# Sheet.net
KiCad netlist of a schematic drawn in Altium Designer
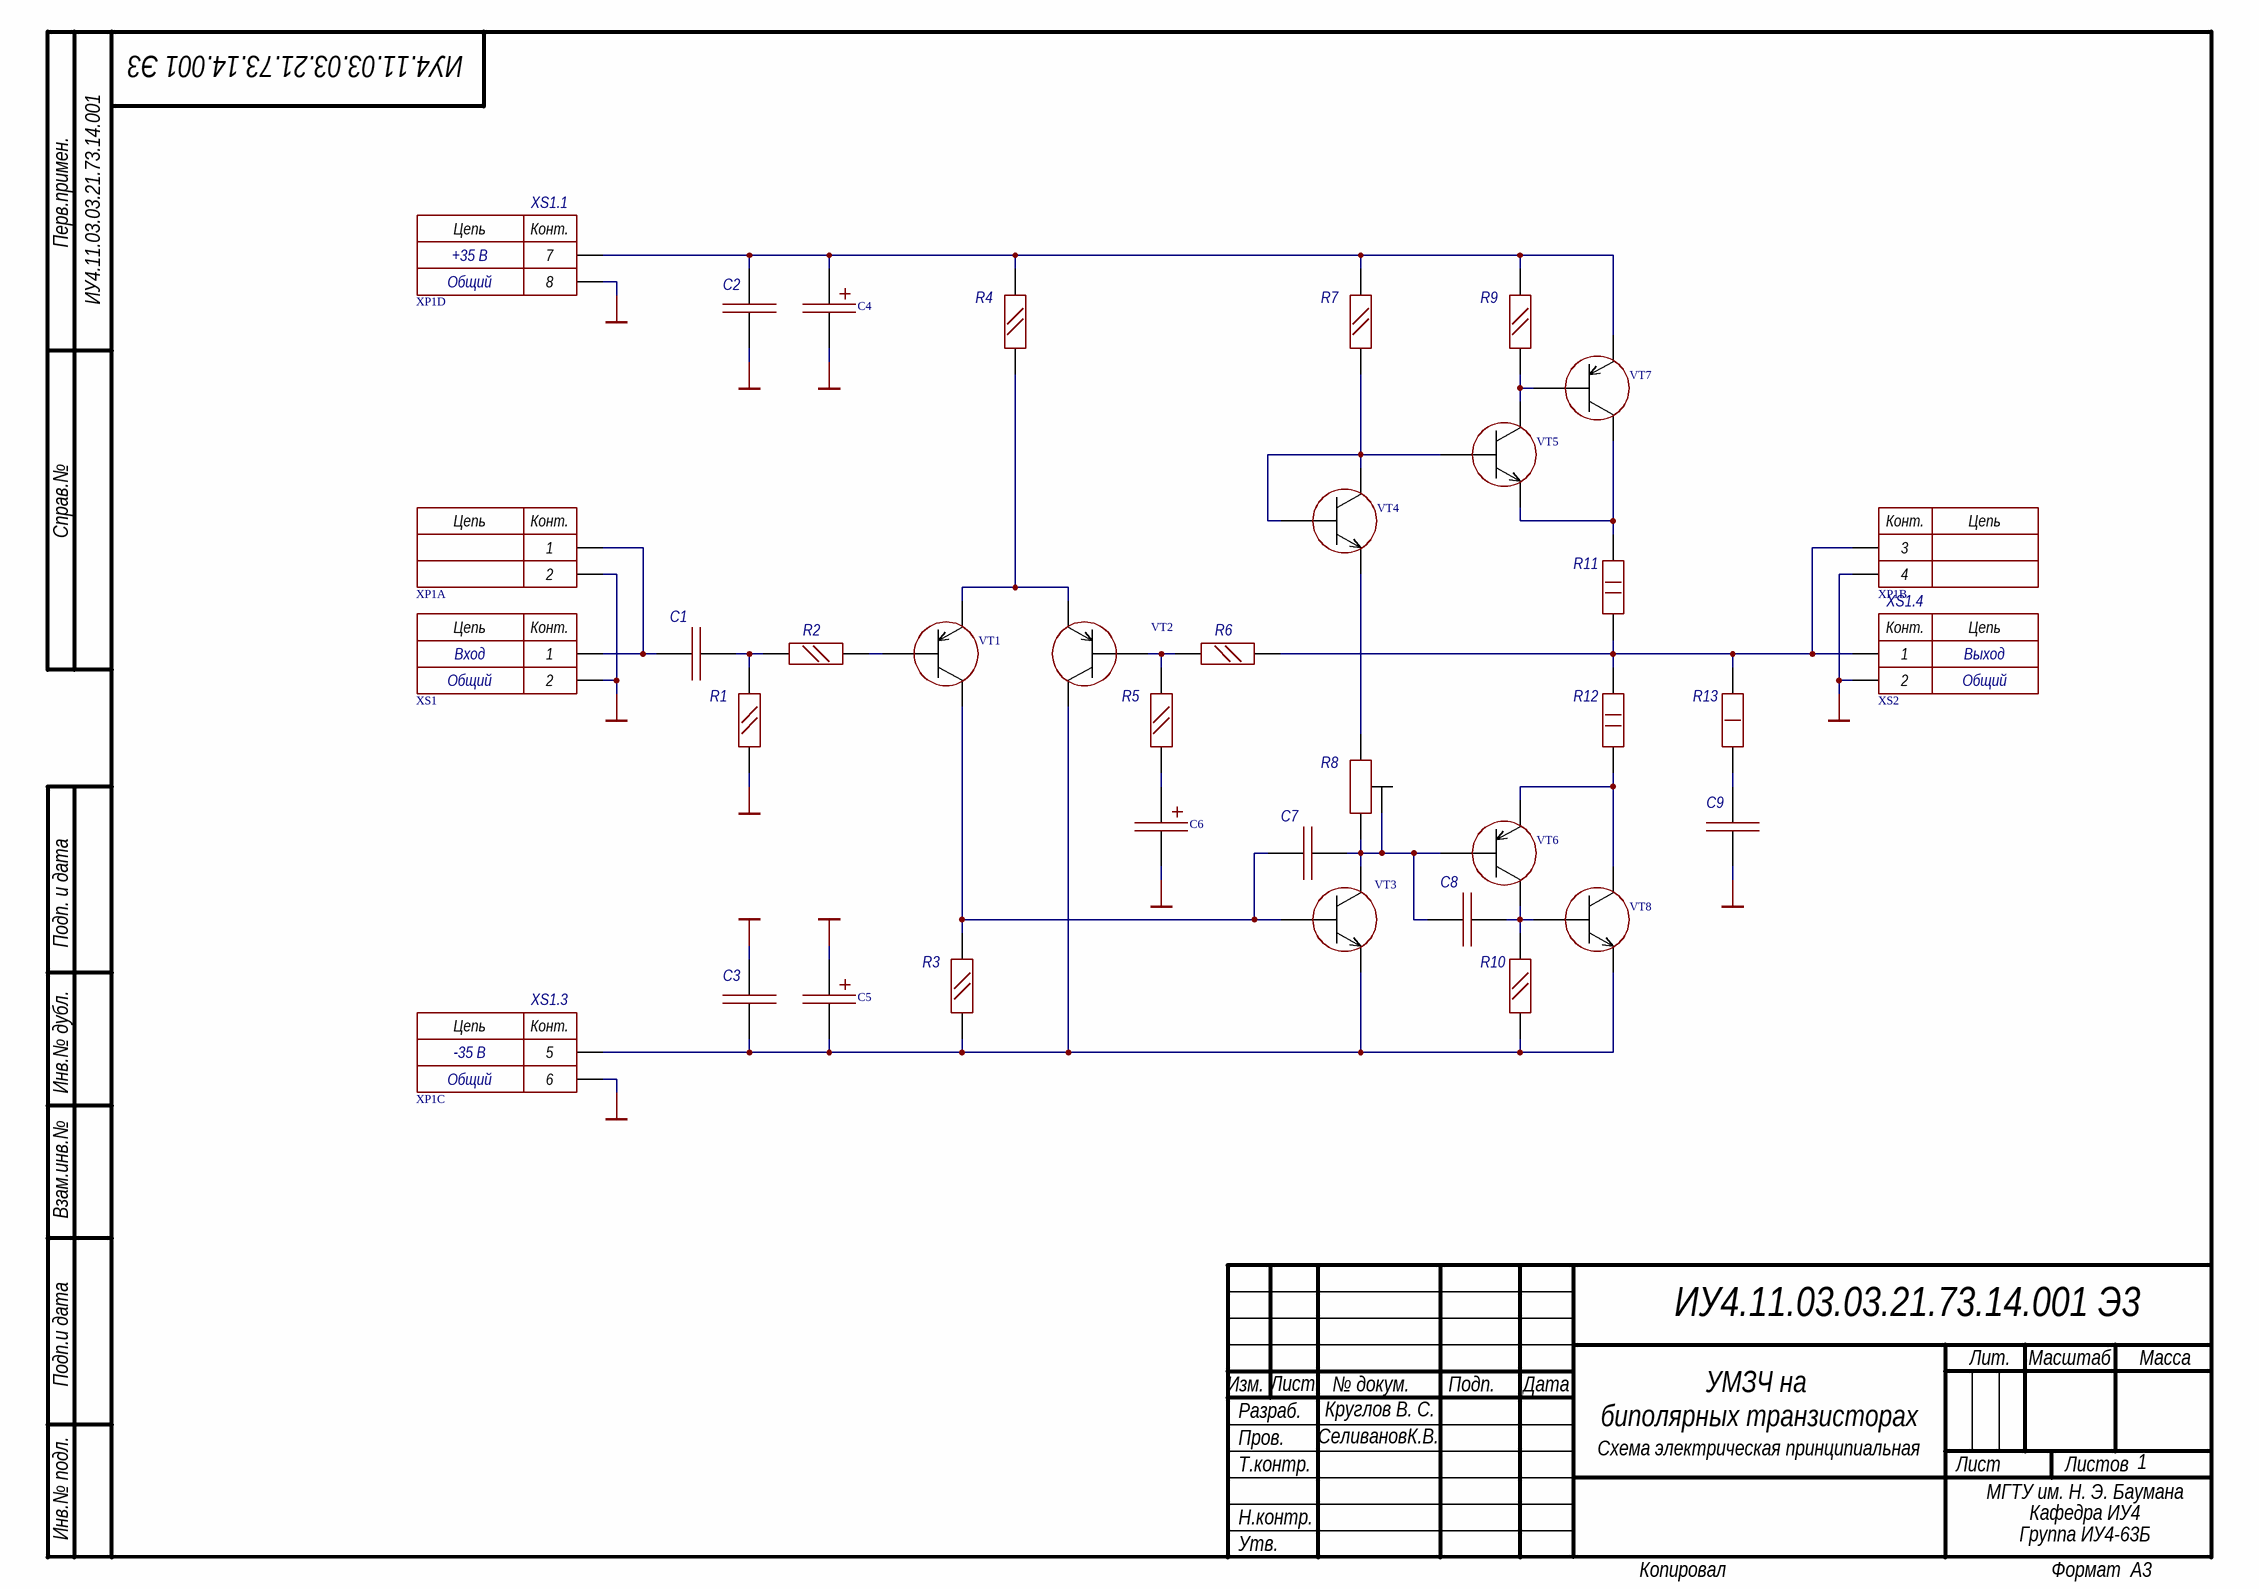
[diagram p0: Sheet.SchDoc]

(export (version "E")
  (design (tool "Eeschema 10.0.6"))
  (components
    (comp (ref "C1")
      (value "Capacitor")
      (footprint "C_PLY_10X5")
      (libsource (lib "Components - 07.07.24 - 20.56") (part "Capacitor"))
    )
    (comp (ref "C2")
      (value "Capacitor")
      (footprint "C_PLY_10X5")
      (libsource (lib "Components - 07.07.24 - 20.56") (part "Capacitor"))
    )
    (comp (ref "C3")
      (value "Capacitor")
      (footprint "C_PLY_10X5")
      (libsource (lib "Components - 07.07.24 - 20.56") (part "Capacitor"))
    )
    (comp (ref "C4")
      (value "Capactor polar")
      (footprint "C_EL_12X25")
      (libsource (lib "Components - 07.07.24 - 20.56") (part "Capactor polar"))
    )
    (comp (ref "C5")
      (value "Capactor polar")
      (footprint "C_EL_12X25")
      (libsource (lib "Components - 07.07.24 - 20.56") (part "Capactor polar"))
    )
    (comp (ref "C6")
      (value "Capactor polar")
      (footprint "C_EL_4X7")
      (libsource (lib "Components - 07.07.24 - 20.56") (part "Capactor polar"))
    )
    (comp (ref "C7")
      (value "Capacitor")
      (footprint "C_PLY_7X5")
      (libsource (lib "Components - 07.07.24 - 20.56") (part "Capacitor"))
    )
    (comp (ref "C8")
      (value "Capacitor")
      (footprint "C_PLY_7X5")
      (libsource (lib "Components - 07.07.24 - 20.56") (part "Capacitor"))
    )
    (comp (ref "C9")
      (value "Capacitor")
      (footprint "C_PLY_10X5")
      (libsource (lib "Components - 07.07.24 - 20.56") (part "Capacitor"))
    )
    (comp (ref "R1")
      (value "Res")
      (footprint "R0125W_AX025")
      (libsource (lib "Integrated_Library_PAAF") (part "Res"))
    )
    (comp (ref "R2") (value "Res") (footprint "R0125W_AX025") (libsource (lib "") (part "Res_1")))
    (comp (ref "R3")
      (value "Res")
      (footprint "R0125W_AX025")
      (libsource (lib "Integrated_Library_PAAF") (part "Res"))
    )
    (comp (ref "R4")
      (value "Res")
      (footprint "R0125W_AX025")
      (libsource (lib "Integrated_Library_PAAF") (part "Res"))
    )
    (comp (ref "R5")
      (value "Res")
      (footprint "R0125W_AX025")
      (libsource (lib "Integrated_Library_PAAF") (part "Res"))
    )
    (comp (ref "R6") (value "Res") (footprint "R0125W_AX025") (libsource (lib "") (part "Res_1")))
    (comp (ref "R7")
      (value "Res")
      (footprint "R0125W_AX025")
      (libsource (lib "Integrated_Library_PAAF") (part "Res"))
    )
    (comp (ref "R8")
      (value "POT")
      (footprint "POT_3296W")
      (libsource (lib "Integrated_Library_PAAF") (part "POT"))
    )
    (comp (ref "R9")
      (value "Res")
      (footprint "R0125W_AX025")
      (libsource (lib "Integrated_Library_PAAF") (part "Res"))
    )
    (comp (ref "R10")
      (value "Res")
      (footprint "R0125W_AX025")
      (libsource (lib "Integrated_Library_PAAF") (part "Res"))
    )
    (comp (ref "R11")
      (value "Res")
      (footprint "R2W_AX08")
      (libsource (lib "Integrated_Library_PAAF") (part "Res"))
    )
    (comp (ref "R12")
      (value "Res")
      (footprint "R2W_AX08")
      (libsource (lib "Integrated_Library_PAAF") (part "Res"))
    )
    (comp (ref "R13")
      (value "Res")
      (footprint "R1W_AX06")
      (libsource (lib "Integrated_Library_PAAF") (part "Res"))
    )
    (comp (ref "VT1")
      (value "Transistor_PNP")
      (footprint "TO92_3FB")
      (libsource (lib "Sch") (part "Transistor_PNP"))
    )
    (comp (ref "VT2")
      (value "Transistor_PNP")
      (footprint "TO92_3FB")
      (libsource (lib "Sch") (part "Transistor_PNP"))
    )
    (comp (ref "VT3")
      (value "BD139G")
      (footprint "TO220_3")
      (libsource (lib "Components - 07.07.24 - 21.07") (part "Transistor_NPN"))
    )
    (comp (ref "VT4")
      (value "BD139G")
      (footprint "TO126_3")
      (libsource (lib "Components - 07.07.24 - 21.07") (part "Transistor_NPN"))
    )
    (comp (ref "VT5")
      (value "BD139G")
      (footprint "TO126_3")
      (libsource (lib "Components - 07.07.24 - 21.07") (part "Transistor_NPN"))
    )
    (comp (ref "VT6")
      (value "Transistor_PNP")
      (footprint "TO126_3")
      (libsource (lib "Sch") (part "Transistor_PNP"))
    )
    (comp (ref "VT7")
      (value "Transistor_PNP")
      (footprint "TO247_3")
      (libsource (lib "Sch") (part "Transistor_PNP"))
    )
    (comp (ref "VT8")
      (value "BD139G")
      (footprint "TO247_3")
      (libsource (lib "Components - 07.07.24 - 21.07") (part "Transistor_NPN"))
    )
    (comp (ref "XP1")
      (value "CONN")
      (footprint "MOLEX_430450821")
      (libsource (lib "Components - 07.07.24 - 20.56") (part "CONN"))
    )
    (comp (ref "XS1")
      (value "Audio")
      (footprint "FP-NMJ4HFD2-MFG")
      (libsource (lib "Integrated_Library_PAAF") (part "Audio"))
    )
    (comp (ref "XS2")
      (value "Audio")
      (footprint "FP-NMJ4HFD2-MFG")
      (libsource (lib "Integrated_Library_PAAF") (part "Audio"))
    )
  )
  (nets
    (net (code "1") (name "GND") (class "Default")
      (node (ref "C2") (pin "2") (pinfunction "2_2") (pintype "passive"))
      (node (ref "C3") (pin "2") (pinfunction "2_2") (pintype "passive"))
      (node (ref "C4") (pin "1") (pinfunction "1_1") (pintype "passive"))
      (node (ref "C5") (pin "2") (pinfunction "2_2") (pintype "passive"))
      (node (ref "C6") (pin "1") (pinfunction "1_1") (pintype "passive"))
      (node (ref "C9") (pin "2") (pinfunction "2_2") (pintype "passive"))
      (node (ref "R1") (pin "1") (pinfunction "1_1") (pintype "passive"))
      (node (ref "XP1") (pin "2") (pintype "passive"))
      (node (ref "XP1") (pin "4") (pintype "passive"))
      (node (ref "XP1") (pin "6") (pintype "passive"))
      (node (ref "XP1") (pin "8") (pintype "passive"))
      (node (ref "XS1") (pin "2") (pintype "passive"))
      (node (ref "XS2") (pin "2") (pintype "passive"))
    )
    (net (code "2") (name "Net-(C1-Pad1)") (class "Default")
      (node (ref "C1") (pin "1") (pinfunction "1_1") (pintype "passive"))
      (node (ref "XP1") (pin "1") (pintype "passive"))
      (node (ref "XS1") (pin "1") (pintype "passive"))
    )
    (net (code "3") (name "Net-(C1-Pad2)") (class "Default")
      (node (ref "C1") (pin "2") (pinfunction "2_2") (pintype "passive"))
      (node (ref "R1") (pin "2") (pinfunction "2_2") (pintype "passive"))
      (node (ref "R2") (pin "2") (pinfunction "2_2") (pintype "passive"))
    )
    (net (code "4") (name "Net-(C6-Pad2)") (class "Default")
      (node (ref "C6") (pin "2") (pinfunction "2_2") (pintype "passive"))
      (node (ref "R5") (pin "1") (pinfunction "1_1") (pintype "passive"))
    )
    (net (code "5") (name "Net-(C9-Pad1)") (class "Default")
      (node (ref "C9") (pin "1") (pinfunction "1_1") (pintype "passive"))
      (node (ref "R13") (pin "1") (pinfunction "1_1") (pintype "passive"))
    )
    (net (code "6") (name "Net-(R11-Pad1)") (class "Default")
      (node (ref "R11") (pin "1") (pinfunction "1_1") (pintype "passive"))
      (node (ref "R12") (pin "2") (pinfunction "2_2") (pintype "passive"))
      (node (ref "R13") (pin "2") (pinfunction "2_2") (pintype "passive"))
      (node (ref "R6") (pin "1") (pinfunction "1_1") (pintype "passive"))
      (node (ref "XP1") (pin "3") (pintype "passive"))
      (node (ref "XS2") (pin "1") (pintype "passive"))
    )
    (net (code "7") (name "Net-(VT1-B)") (class "Default")
      (node (ref "R2") (pin "1") (pinfunction "1_1") (pintype "passive"))
      (node (ref "VT1") (pin "3") (pinfunction "B_3") (pintype "passive"))
    )
    (net (code "8") (name "Net-(VT1-C)") (class "Default")
      (node (ref "C7") (pin "1") (pinfunction "1_1") (pintype "passive"))
      (node (ref "R3") (pin "2") (pinfunction "2_2") (pintype "passive"))
      (node (ref "VT1") (pin "2") (pinfunction "C_2") (pintype "passive"))
      (node (ref "VT3") (pin "3") (pinfunction "B_3") (pintype "passive"))
    )
    (net (code "9") (name "Net-(VT1-E)") (class "Default")
      (node (ref "R4") (pin "1") (pinfunction "1_1") (pintype "passive"))
      (node (ref "VT1") (pin "1") (pinfunction "E_1") (pintype "passive"))
      (node (ref "VT2") (pin "1") (pinfunction "E_1") (pintype "passive"))
    )
    (net (code "10") (name "Net-(VT2-B)") (class "Default")
      (node (ref "R5") (pin "2") (pinfunction "2_2") (pintype "passive"))
      (node (ref "R6") (pin "2") (pinfunction "2_2") (pintype "passive"))
      (node (ref "VT2") (pin "3") (pinfunction "B_3") (pintype "passive"))
    )
    (net (code "11") (name "Net-(VT2-C)") (class "Default")
      (node (ref "C3") (pin "1") (pinfunction "1_1") (pintype "passive"))
      (node (ref "C5") (pin "1") (pinfunction "1_1") (pintype "passive"))
      (node (ref "R10") (pin "1") (pinfunction "1_1") (pintype "passive"))
      (node (ref "R3") (pin "1") (pinfunction "1_1") (pintype "passive"))
      (node (ref "VT2") (pin "2") (pinfunction "C_2") (pintype "passive"))
      (node (ref "VT3") (pin "1") (pinfunction "E_1") (pintype "passive"))
      (node (ref "VT8") (pin "1") (pinfunction "E_1") (pintype "passive"))
      (node (ref "XP1") (pin "5") (pintype "passive"))
    )
    (net (code "12") (name "Net-(VT3-C)") (class "Default")
      (node (ref "C7") (pin "2") (pinfunction "2_2") (pintype "passive"))
      (node (ref "C8") (pin "1") (pinfunction "1_1") (pintype "passive"))
      (node (ref "R8") (pin "2") (pinfunction "2_2") (pintype "passive"))
      (node (ref "R8") (pin "3") (pinfunction "3_3") (pintype "passive"))
      (node (ref "VT3") (pin "2") (pinfunction "C_2") (pintype "passive"))
      (node (ref "VT6") (pin "3") (pinfunction "B_3") (pintype "passive"))
    )
    (net (code "13") (name "Net-(VT4-B)") (class "Default")
      (node (ref "R7") (pin "1") (pinfunction "1_1") (pintype "passive"))
      (node (ref "VT4") (pin "2") (pinfunction "C_2") (pintype "passive"))
      (node (ref "VT4") (pin "3") (pinfunction "B_3") (pintype "passive"))
      (node (ref "VT5") (pin "3") (pinfunction "B_3") (pintype "passive"))
    )
    (net (code "14") (name "Net-(VT4-E)") (class "Default")
      (node (ref "R8") (pin "1") (pinfunction "1_1") (pintype "passive"))
      (node (ref "VT4") (pin "1") (pinfunction "E_1") (pintype "passive"))
    )
    (net (code "15") (name "Net-(VT5-C)") (class "Default")
      (node (ref "R9") (pin "1") (pinfunction "1_1") (pintype "passive"))
      (node (ref "VT5") (pin "2") (pinfunction "C_2") (pintype "passive"))
      (node (ref "VT7") (pin "3") (pinfunction "B_3") (pintype "passive"))
    )
    (net (code "16") (name "Net-(VT5-E)") (class "Default")
      (node (ref "R11") (pin "2") (pinfunction "2_2") (pintype "passive"))
      (node (ref "VT5") (pin "1") (pinfunction "E_1") (pintype "passive"))
      (node (ref "VT7") (pin "2") (pinfunction "C_2") (pintype "passive"))
    )
    (net (code "17") (name "Net-(VT6-C)") (class "Default")
      (node (ref "C8") (pin "2") (pinfunction "2_2") (pintype "passive"))
      (node (ref "R10") (pin "2") (pinfunction "2_2") (pintype "passive"))
      (node (ref "VT6") (pin "2") (pinfunction "C_2") (pintype "passive"))
      (node (ref "VT8") (pin "3") (pinfunction "B_3") (pintype "passive"))
    )
    (net (code "18") (name "Net-(VT6-E)") (class "Default")
      (node (ref "R12") (pin "1") (pinfunction "1_1") (pintype "passive"))
      (node (ref "VT6") (pin "1") (pinfunction "E_1") (pintype "passive"))
      (node (ref "VT8") (pin "2") (pinfunction "C_2") (pintype "passive"))
    )
    (net (code "19") (name "Net-(VT7-E)") (class "Default")
      (node (ref "C2") (pin "1") (pinfunction "1_1") (pintype "passive"))
      (node (ref "C4") (pin "2") (pinfunction "2_2") (pintype "passive"))
      (node (ref "R4") (pin "2") (pinfunction "2_2") (pintype "passive"))
      (node (ref "R7") (pin "2") (pinfunction "2_2") (pintype "passive"))
      (node (ref "R9") (pin "2") (pinfunction "2_2") (pintype "passive"))
      (node (ref "VT7") (pin "1") (pinfunction "E_1") (pintype "passive"))
      (node (ref "XP1") (pin "7") (pintype "passive"))
    )
  )
)
